# AB.net
KiCad netlist of a schematic drawn in EAGLE
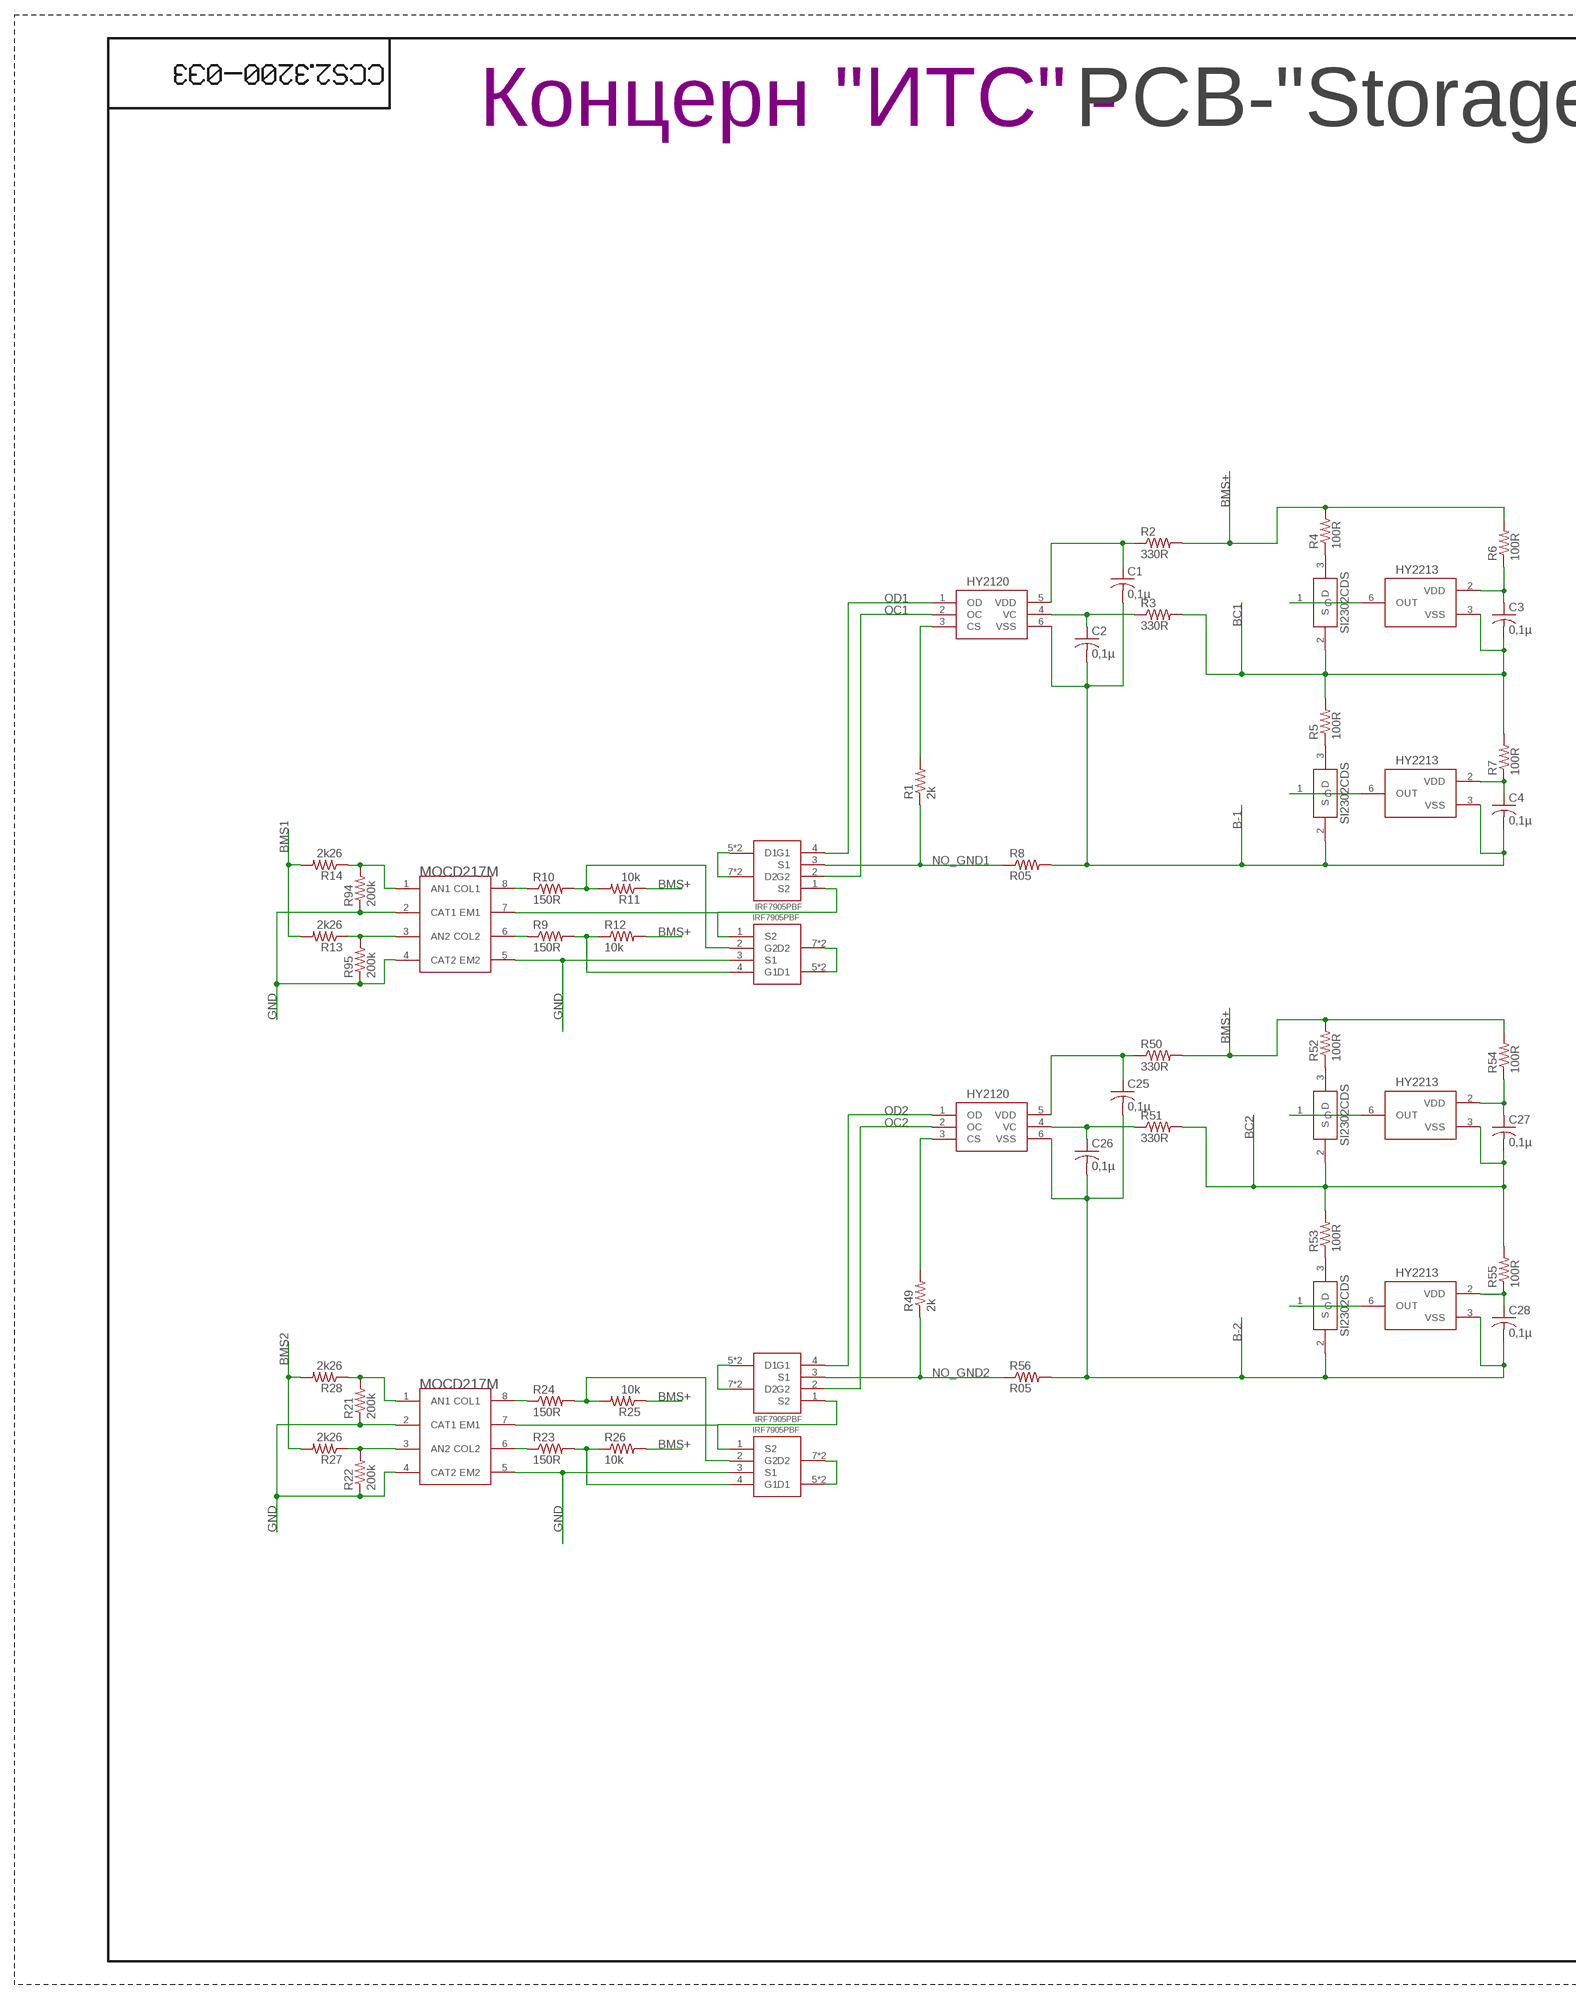
[diagram p0: schematic, sheet 1, part 1 of 2]
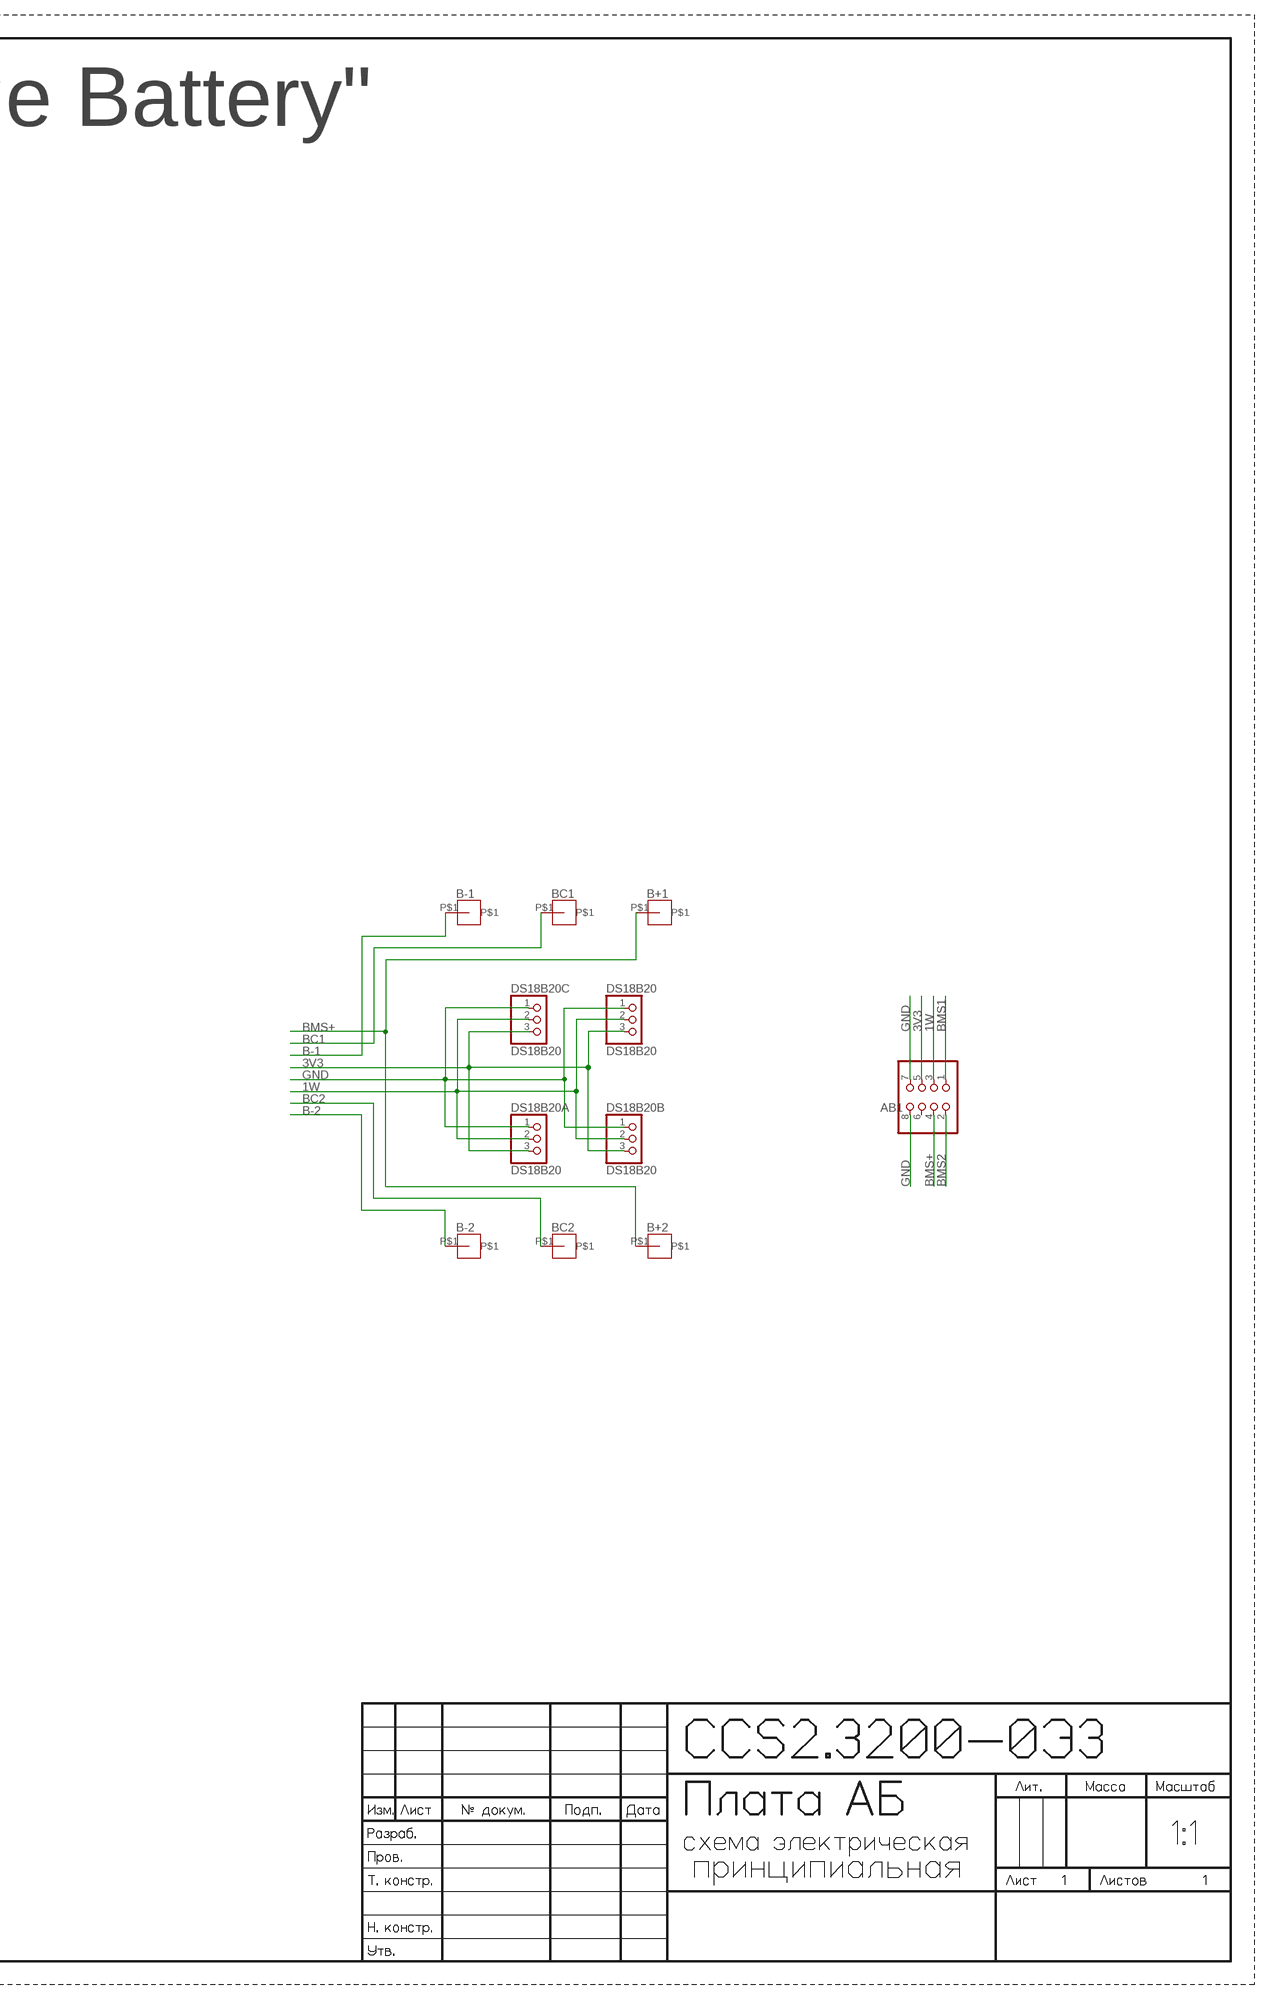
[diagram p1: schematic, sheet 1, part 2 of 2]

(export (version "E")
  (design (tool "Eeschema 10.0.6"))
  (components
    (comp (ref "AB1")
      (value "PINHD-2X4")
      (footprint "eagle-import:2X04")
      (libsource (lib "eagle-import") (part "PINHD-2X4"))
    )
    (comp (ref "B+1")
      (value "BATTERY")
      (footprint "eagle-import:BATTERY")
      (libsource (lib "eagle-import") (part "BATTERY"))
    )
    (comp (ref "B+2")
      (value "BATTERY")
      (footprint "eagle-import:BATTERY")
      (libsource (lib "eagle-import") (part "BATTERY"))
    )
    (comp (ref "B-1")
      (value "BATTERY")
      (footprint "eagle-import:BATTERY")
      (libsource (lib "eagle-import") (part "BATTERY"))
    )
    (comp (ref "B-2")
      (value "BATTERY")
      (footprint "eagle-import:BATTERY")
      (libsource (lib "eagle-import") (part "BATTERY"))
    )
    (comp (ref "BC1")
      (value "BATTERY")
      (footprint "eagle-import:BATTERY")
      (libsource (lib "eagle-import") (part "BATTERY"))
    )
    (comp (ref "BC2")
      (value "BATTERY")
      (footprint "eagle-import:BATTERY")
      (libsource (lib "eagle-import") (part "BATTERY"))
    )
    (comp (ref "C1")
      (value "0,1µ")
      (footprint "eagle-import:C0603")
      (libsource (lib "eagle-import") (part "C-USC0603"))
    )
    (comp (ref "C2")
      (value "0,1µ")
      (footprint "eagle-import:C0603")
      (libsource (lib "eagle-import") (part "C-USC0603"))
    )
    (comp (ref "C3")
      (value "0,1µ")
      (footprint "eagle-import:C0603")
      (libsource (lib "eagle-import") (part "C-USC0603"))
    )
    (comp (ref "C4")
      (value "0,1µ")
      (footprint "eagle-import:C0603")
      (libsource (lib "eagle-import") (part "C-USC0603"))
    )
    (comp (ref "C25")
      (value "0,1µ")
      (footprint "eagle-import:C0603")
      (libsource (lib "eagle-import") (part "C-USC0603"))
    )
    (comp (ref "C26")
      (value "0,1µ")
      (footprint "eagle-import:C0603")
      (libsource (lib "eagle-import") (part "C-USC0603"))
    )
    (comp (ref "C27")
      (value "0,1µ")
      (footprint "eagle-import:C0603")
      (libsource (lib "eagle-import") (part "C-USC0603"))
    )
    (comp (ref "C28")
      (value "0,1µ")
      (footprint "eagle-import:C0603")
      (libsource (lib "eagle-import") (part "C-USC0603"))
    )
    (comp (ref "DS18B20")
      (value "DS18B20")
      (footprint "eagle-import:CONNECT1X3")
      (libsource (lib "eagle-import") (part "CONNECT1X3"))
    )
    (comp (ref "DS18B20A")
      (value "DS18B20")
      (footprint "eagle-import:CONNECT1X3")
      (libsource (lib "eagle-import") (part "CONNECT1X3"))
    )
    (comp (ref "DS18B20B")
      (value "DS18B20")
      (footprint "eagle-import:CONNECT1X3")
      (libsource (lib "eagle-import") (part "CONNECT1X3"))
    )
    (comp (ref "DS18B20C")
      (value "DS18B20")
      (footprint "eagle-import:CONNECT1X3")
      (libsource (lib "eagle-import") (part "CONNECT1X3"))
    )
    (comp (ref "R1")
      (value "2k")
      (footprint "eagle-import:R0603")
      (libsource (lib "eagle-import") (part "resistor_348_R-US_R0603"))
    )
    (comp (ref "R2")
      (value "330R")
      (footprint "eagle-import:R0603")
      (libsource (lib "eagle-import") (part "resistor_348_R-US_R0603"))
    )
    (comp (ref "R3")
      (value "330R")
      (footprint "eagle-import:R0603")
      (libsource (lib "eagle-import") (part "resistor_348_R-US_R0603"))
    )
    (comp (ref "R4")
      (value "100R")
      (footprint "eagle-import:R0603")
      (libsource (lib "eagle-import") (part "resistor_348_R-US_R0603"))
    )
    (comp (ref "R5")
      (value "100R")
      (footprint "eagle-import:R0603")
      (libsource (lib "eagle-import") (part "resistor_348_R-US_R0603"))
    )
    (comp (ref "R6")
      (value "100R")
      (footprint "eagle-import:R0603")
      (libsource (lib "eagle-import") (part "resistor_348_R-US_R0603"))
    )
    (comp (ref "R7")
      (value "100R")
      (footprint "eagle-import:R0603")
      (libsource (lib "eagle-import") (part "resistor_348_R-US_R0603"))
    )
    (comp (ref "R8")
      (value "R05")
      (footprint "eagle-import:R2512")
      (libsource (lib "eagle-import") (part "R-US_R2512"))
    )
    (comp (ref "R9")
      (value "150R")
      (footprint "eagle-import:R0603")
      (libsource (lib "eagle-import") (part "resistor_348_R-US_R0603"))
    )
    (comp (ref "R10")
      (value "150R")
      (footprint "eagle-import:R0603")
      (libsource (lib "eagle-import") (part "resistor_348_R-US_R0603"))
    )
    (comp (ref "R11")
      (value "10k")
      (footprint "eagle-import:R0603")
      (libsource (lib "eagle-import") (part "resistor_348_R-US_R0603"))
    )
    (comp (ref "R12")
      (value "10k")
      (footprint "eagle-import:R0603")
      (libsource (lib "eagle-import") (part "resistor_348_R-US_R0603"))
    )
    (comp (ref "R13")
      (value "2k26")
      (footprint "eagle-import:R0603")
      (libsource (lib "eagle-import") (part "resistor_348_R-US_R0603"))
    )
    (comp (ref "R14")
      (value "2k26")
      (footprint "eagle-import:R0603")
      (libsource (lib "eagle-import") (part "resistor_348_R-US_R0603"))
    )
    (comp (ref "R21")
      (value "200k")
      (footprint "eagle-import:R0603")
      (libsource (lib "eagle-import") (part "resistor_348_R-US_R0603"))
    )
    (comp (ref "R22")
      (value "200k")
      (footprint "eagle-import:R0603")
      (libsource (lib "eagle-import") (part "resistor_348_R-US_R0603"))
    )
    (comp (ref "R23")
      (value "150R")
      (footprint "eagle-import:R0603")
      (libsource (lib "eagle-import") (part "resistor_348_R-US_R0603"))
    )
    (comp (ref "R24")
      (value "150R")
      (footprint "eagle-import:R0603")
      (libsource (lib "eagle-import") (part "resistor_348_R-US_R0603"))
    )
    (comp (ref "R25")
      (value "10k")
      (footprint "eagle-import:R0603")
      (libsource (lib "eagle-import") (part "resistor_348_R-US_R0603"))
    )
    (comp (ref "R26")
      (value "10k")
      (footprint "eagle-import:R0603")
      (libsource (lib "eagle-import") (part "resistor_348_R-US_R0603"))
    )
    (comp (ref "R27")
      (value "2k26")
      (footprint "eagle-import:R0603")
      (libsource (lib "eagle-import") (part "resistor_348_R-US_R0603"))
    )
    (comp (ref "R28")
      (value "2k26")
      (footprint "eagle-import:R0603")
      (libsource (lib "eagle-import") (part "resistor_348_R-US_R0603"))
    )
    (comp (ref "R49")
      (value "2k")
      (footprint "eagle-import:R0603")
      (libsource (lib "eagle-import") (part "resistor_348_R-US_R0603"))
    )
    (comp (ref "R50")
      (value "330R")
      (footprint "eagle-import:R0603")
      (libsource (lib "eagle-import") (part "resistor_348_R-US_R0603"))
    )
    (comp (ref "R51")
      (value "330R")
      (footprint "eagle-import:R0603")
      (libsource (lib "eagle-import") (part "resistor_348_R-US_R0603"))
    )
    (comp (ref "R52")
      (value "100R")
      (footprint "eagle-import:R0603")
      (libsource (lib "eagle-import") (part "resistor_348_R-US_R0603"))
    )
    (comp (ref "R53")
      (value "100R")
      (footprint "eagle-import:R0603")
      (libsource (lib "eagle-import") (part "resistor_348_R-US_R0603"))
    )
    (comp (ref "R54")
      (value "100R")
      (footprint "eagle-import:R0603")
      (libsource (lib "eagle-import") (part "resistor_348_R-US_R0603"))
    )
    (comp (ref "R55")
      (value "100R")
      (footprint "eagle-import:R0603")
      (libsource (lib "eagle-import") (part "resistor_348_R-US_R0603"))
    )
    (comp (ref "R56")
      (value "R05")
      (footprint "eagle-import:R2512")
      (libsource (lib "eagle-import") (part "R-US_R2512"))
    )
    (comp (ref "R94")
      (value "200k")
      (footprint "eagle-import:R0603")
      (libsource (lib "eagle-import") (part "resistor_348_R-US_R0603"))
    )
    (comp (ref "R95")
      (value "200k")
      (footprint "eagle-import:R0603")
      (libsource (lib "eagle-import") (part "resistor_348_R-US_R0603"))
    )
    (comp (ref "U$1")
      (value "PCB-\"Storage Battery\"")
      (footprint "eagle-import:ITS-LOGO")
      (libsource (lib "eagle-import") (part "ITS-LOGOPCB-{dblquote}{dblquote}"))
    )
    (comp (ref "U$2")
      (value "MOCD217M")
      (footprint "eagle-import:SOIC8")
      (libsource (lib "eagle-import") (part "MOCD217M"))
    )
    (comp (ref "U$3")
      (value "HY2120")
      (footprint "eagle-import:SOT23-6")
      (libsource (lib "eagle-import") (part "HY2120"))
    )
    (comp (ref "U$4")
      (value "HY2213\"")
      (footprint "eagle-import:SOT23-6")
      (libsource (lib "eagle-import") (part "HY2213{dblquote}"))
    )
    (comp (ref "U$5")
      (value "HY2213\"")
      (footprint "eagle-import:SOT23-6")
      (libsource (lib "eagle-import") (part "HY2213{dblquote}"))
    )
    (comp (ref "U$6")
      (value "SI2302CDS")
      (footprint "eagle-import:SOT23-3")
      (libsource (lib "eagle-import") (part "SI2302CDS"))
    )
    (comp (ref "U$7")
      (value "SI2302CDS")
      (footprint "eagle-import:SOT23-3")
      (libsource (lib "eagle-import") (part "SI2302CDS"))
    )
    (comp (ref "U$8")
      (value "IRF7905PBF")
      (footprint "eagle-import:SO8")
      (libsource (lib "eagle-import") (part "IRF7905PBF"))
    )
    (comp (ref "U$9")
      (value "IRF7905PBF")
      (footprint "eagle-import:SO8")
      (libsource (lib "eagle-import") (part "IRF7905PBF"))
    )
    (comp (ref "U$11")
      (value "MOCD217M")
      (footprint "eagle-import:SOIC8")
      (libsource (lib "eagle-import") (part "MOCD217M"))
    )
    (comp (ref "U$12")
      (value "IRF7905PBF")
      (footprint "eagle-import:SO8")
      (libsource (lib "eagle-import") (part "IRF7905PBF"))
    )
    (comp (ref "U$13")
      (value "IRF7905PBF")
      (footprint "eagle-import:SO8")
      (libsource (lib "eagle-import") (part "IRF7905PBF"))
    )
    (comp (ref "U$45")
      (value "HY2120")
      (footprint "eagle-import:SOT23-6")
      (libsource (lib "eagle-import") (part "HY2120"))
    )
    (comp (ref "U$46")
      (value "HY2213\"")
      (footprint "eagle-import:SOT23-6")
      (libsource (lib "eagle-import") (part "HY2213{dblquote}"))
    )
    (comp (ref "U$47")
      (value "HY2213\"")
      (footprint "eagle-import:SOT23-6")
      (libsource (lib "eagle-import") (part "HY2213{dblquote}"))
    )
    (comp (ref "U$48")
      (value "SI2302CDS")
      (footprint "eagle-import:SOT23-3")
      (libsource (lib "eagle-import") (part "SI2302CDS"))
    )
    (comp (ref "U$49")
      (value "SI2302CDS")
      (footprint "eagle-import:SOT23-3")
      (libsource (lib "eagle-import") (part "SI2302CDS"))
    )
  )
  (nets
    (net (code "1") (name "/1W") (class "Default")
      (node (ref "AB1") (pin "3") (pinfunction "3_3") (pintype "passive"))
      (node (ref "DS18B20") (pin "2") (pinfunction "2_2") (pintype "passive"))
      (node (ref "DS18B20A") (pin "2") (pinfunction "2_2") (pintype "passive"))
      (node (ref "DS18B20B") (pin "2") (pinfunction "2_2") (pintype "passive"))
      (node (ref "DS18B20C") (pin "2") (pinfunction "2_2") (pintype "passive"))
    )
    (net (code "2") (name "/3V3") (class "Default")
      (node (ref "AB1") (pin "5") (pinfunction "5_5") (pintype "passive"))
      (node (ref "DS18B20") (pin "3") (pinfunction "3_3") (pintype "passive"))
      (node (ref "DS18B20A") (pin "3") (pinfunction "3_3") (pintype "passive"))
      (node (ref "DS18B20B") (pin "3") (pinfunction "3_3") (pintype "passive"))
      (node (ref "DS18B20C") (pin "3") (pinfunction "3_3") (pintype "passive"))
    )
    (net (code "3") (name "/B-1") (class "Default")
      (node (ref "B-1") (pin "P$1") (pinfunction "P$1_P$1") (pintype "bidirectional"))
      (node (ref "C1") (pin "2") (pinfunction "2_2") (pintype "passive"))
      (node (ref "C2") (pin "2") (pinfunction "2_2") (pintype "passive"))
      (node (ref "C4") (pin "2") (pinfunction "2_2") (pintype "passive"))
      (node (ref "R8") (pin "2") (pinfunction "2_2") (pintype "passive"))
      (node (ref "U$3") (pin "6") (pinfunction "VSS_6") (pintype "bidirectional"))
      (node (ref "U$5") (pin "3") (pinfunction "VSS_3") (pintype "bidirectional"))
      (node (ref "U$7") (pin "2") (pinfunction "S_2") (pintype "bidirectional"))
    )
    (net (code "4") (name "/B-2") (class "Default")
      (node (ref "B-2") (pin "P$1") (pinfunction "P$1_P$1") (pintype "bidirectional"))
      (node (ref "C25") (pin "2") (pinfunction "2_2") (pintype "passive"))
      (node (ref "C26") (pin "2") (pinfunction "2_2") (pintype "passive"))
      (node (ref "C28") (pin "2") (pinfunction "2_2") (pintype "passive"))
      (node (ref "R56") (pin "2") (pinfunction "2_2") (pintype "passive"))
      (node (ref "U$45") (pin "6") (pinfunction "VSS_6") (pintype "bidirectional"))
      (node (ref "U$47") (pin "3") (pinfunction "VSS_3") (pintype "bidirectional"))
      (node (ref "U$49") (pin "2") (pinfunction "S_2") (pintype "bidirectional"))
    )
    (net (code "5") (name "/BC1") (class "Default")
      (node (ref "BC1") (pin "P$1") (pinfunction "P$1_P$1") (pintype "bidirectional"))
      (node (ref "C3") (pin "2") (pinfunction "2_2") (pintype "passive"))
      (node (ref "R3") (pin "2") (pinfunction "2_2") (pintype "passive"))
      (node (ref "R5") (pin "2") (pinfunction "2_2") (pintype "passive"))
      (node (ref "R7") (pin "2") (pinfunction "2_2") (pintype "passive"))
      (node (ref "U$4") (pin "3") (pinfunction "VSS_3") (pintype "bidirectional"))
      (node (ref "U$6") (pin "2") (pinfunction "S_2") (pintype "bidirectional"))
    )
    (net (code "6") (name "/BC2") (class "Default")
      (node (ref "BC2") (pin "P$1") (pinfunction "P$1_P$1") (pintype "bidirectional"))
      (node (ref "C27") (pin "2") (pinfunction "2_2") (pintype "passive"))
      (node (ref "R51") (pin "2") (pinfunction "2_2") (pintype "passive"))
      (node (ref "R53") (pin "2") (pinfunction "2_2") (pintype "passive"))
      (node (ref "R55") (pin "2") (pinfunction "2_2") (pintype "passive"))
      (node (ref "U$46") (pin "3") (pinfunction "VSS_3") (pintype "bidirectional"))
      (node (ref "U$48") (pin "2") (pinfunction "S_2") (pintype "bidirectional"))
    )
    (net (code "7") (name "/BMS+") (class "Default")
      (node (ref "AB1") (pin "4") (pinfunction "4_4") (pintype "passive"))
      (node (ref "B+1") (pin "P$1") (pinfunction "P$1_P$1") (pintype "bidirectional"))
      (node (ref "B+2") (pin "P$1") (pinfunction "P$1_P$1") (pintype "bidirectional"))
      (node (ref "R11") (pin "1") (pinfunction "1_1") (pintype "passive"))
      (node (ref "R12") (pin "2") (pinfunction "2_2") (pintype "passive"))
      (node (ref "R2") (pin "2") (pinfunction "2_2") (pintype "passive"))
      (node (ref "R25") (pin "1") (pinfunction "1_1") (pintype "passive"))
      (node (ref "R26") (pin "2") (pinfunction "2_2") (pintype "passive"))
      (node (ref "R4") (pin "2") (pinfunction "2_2") (pintype "passive"))
      (node (ref "R50") (pin "2") (pinfunction "2_2") (pintype "passive"))
      (node (ref "R52") (pin "2") (pinfunction "2_2") (pintype "passive"))
      (node (ref "R54") (pin "2") (pinfunction "2_2") (pintype "passive"))
      (node (ref "R6") (pin "2") (pinfunction "2_2") (pintype "passive"))
    )
    (net (code "8") (name "/BMS1") (class "Default")
      (node (ref "AB1") (pin "1") (pinfunction "1_1") (pintype "passive"))
      (node (ref "R13") (pin "2") (pinfunction "2_2") (pintype "passive"))
      (node (ref "R14") (pin "2") (pinfunction "2_2") (pintype "passive"))
    )
    (net (code "9") (name "/BMS2") (class "Default")
      (node (ref "AB1") (pin "2") (pinfunction "2_2") (pintype "passive"))
      (node (ref "R27") (pin "2") (pinfunction "2_2") (pintype "passive"))
      (node (ref "R28") (pin "2") (pinfunction "2_2") (pintype "passive"))
    )
    (net (code "10") (name "/GND") (class "Default")
      (node (ref "AB1") (pin "7") (pinfunction "7_7") (pintype "passive"))
      (node (ref "AB1") (pin "8") (pinfunction "8_8") (pintype "passive"))
      (node (ref "DS18B20") (pin "1") (pinfunction "1_1") (pintype "passive"))
      (node (ref "DS18B20A") (pin "1") (pinfunction "1_1") (pintype "passive"))
      (node (ref "DS18B20B") (pin "1") (pinfunction "1_1") (pintype "passive"))
      (node (ref "DS18B20C") (pin "1") (pinfunction "1_1") (pintype "passive"))
      (node (ref "R21") (pin "1") (pinfunction "1_1") (pintype "passive"))
      (node (ref "R22") (pin "1") (pinfunction "1_1") (pintype "passive"))
      (node (ref "R94") (pin "1") (pinfunction "1_1") (pintype "passive"))
      (node (ref "R95") (pin "1") (pinfunction "1_1") (pintype "passive"))
      (node (ref "U$11") (pin "2") (pinfunction "CAT1_2") (pintype "bidirectional"))
      (node (ref "U$11") (pin "4") (pinfunction "CAT2_4") (pintype "bidirectional"))
      (node (ref "U$11") (pin "5") (pinfunction "EM2_5") (pintype "bidirectional"))
      (node (ref "U$12") (pin "3") (pinfunction "S1_3") (pintype "bidirectional"))
      (node (ref "U$2") (pin "2") (pinfunction "CAT1_2") (pintype "bidirectional"))
      (node (ref "U$2") (pin "4") (pinfunction "CAT2_4") (pintype "bidirectional"))
      (node (ref "U$2") (pin "5") (pinfunction "EM2_5") (pintype "bidirectional"))
      (node (ref "U$8") (pin "3") (pinfunction "S1_3") (pintype "bidirectional"))
    )
    (net (code "11") (name "/NO_GND1") (class "Default")
      (node (ref "R1") (pin "1") (pinfunction "1_1") (pintype "passive"))
      (node (ref "R8") (pin "1") (pinfunction "1_1") (pintype "passive"))
      (node (ref "U$9") (pin "3") (pinfunction "S1_3") (pintype "bidirectional"))
    )
    (net (code "12") (name "/NO_GND2") (class "Default")
      (node (ref "R49") (pin "1") (pinfunction "1_1") (pintype "passive"))
      (node (ref "R56") (pin "1") (pinfunction "1_1") (pintype "passive"))
      (node (ref "U$13") (pin "3") (pinfunction "S1_3") (pintype "bidirectional"))
    )
    (net (code "13") (name "/OC1") (class "Default")
      (node (ref "U$3") (pin "2") (pinfunction "OC_2") (pintype "bidirectional"))
      (node (ref "U$9") (pin "2") (pinfunction "G2_2") (pintype "bidirectional"))
    )
    (net (code "14") (name "/OC2") (class "Default")
      (node (ref "U$13") (pin "2") (pinfunction "G2_2") (pintype "bidirectional"))
      (node (ref "U$45") (pin "2") (pinfunction "OC_2") (pintype "bidirectional"))
    )
    (net (code "15") (name "/OD1") (class "Default")
      (node (ref "U$3") (pin "1") (pinfunction "OD_1") (pintype "bidirectional"))
      (node (ref "U$9") (pin "4") (pinfunction "G1_4") (pintype "bidirectional"))
    )
    (net (code "16") (name "/OD2") (class "Default")
      (node (ref "U$13") (pin "4") (pinfunction "G1_4") (pintype "bidirectional"))
      (node (ref "U$45") (pin "1") (pinfunction "OD_1") (pintype "bidirectional"))
    )
    (net (code "17") (name "Net-(U$2-AN1)") (class "Default")
      (node (ref "R14") (pin "1") (pinfunction "1_1") (pintype "passive"))
      (node (ref "R94") (pin "2") (pinfunction "2_2") (pintype "passive"))
      (node (ref "U$2") (pin "1") (pinfunction "AN1_1") (pintype "bidirectional"))
    )
    (net (code "18") (name "Net-(U$2-AN2)") (class "Default")
      (node (ref "R13") (pin "1") (pinfunction "1_1") (pintype "passive"))
      (node (ref "R95") (pin "2") (pinfunction "2_2") (pintype "passive"))
      (node (ref "U$2") (pin "3") (pinfunction "AN2_3") (pintype "bidirectional"))
    )
    (net (code "19") (name "Net-(U$2-COL1)") (class "Default")
      (node (ref "R10") (pin "1") (pinfunction "1_1") (pintype "passive"))
      (node (ref "U$2") (pin "8") (pinfunction "COL1_8") (pintype "bidirectional"))
    )
    (net (code "20") (name "Net-(U$2-COL2)") (class "Default")
      (node (ref "R9") (pin "1") (pinfunction "1_1") (pintype "passive"))
      (node (ref "U$2") (pin "6") (pinfunction "COL2_6") (pintype "bidirectional"))
    )
    (net (code "21") (name "Net-(U$2-EM1)") (class "Default")
      (node (ref "U$2") (pin "7") (pinfunction "EM1_7") (pintype "bidirectional"))
      (node (ref "U$8") (pin "1") (pinfunction "S2_1") (pintype "bidirectional"))
      (node (ref "U$9") (pin "1") (pinfunction "S2_1") (pintype "bidirectional"))
    )
    (net (code "22") (name "Net-(U$3-CS)") (class "Default")
      (node (ref "R1") (pin "2") (pinfunction "2_2") (pintype "passive"))
      (node (ref "U$3") (pin "3") (pinfunction "CS_3") (pintype "bidirectional"))
    )
    (net (code "23") (name "Net-(U$3-VC)") (class "Default")
      (node (ref "C2") (pin "1") (pinfunction "1_1") (pintype "passive"))
      (node (ref "R3") (pin "1") (pinfunction "1_1") (pintype "passive"))
      (node (ref "U$3") (pin "4") (pinfunction "VC_4") (pintype "bidirectional"))
    )
    (net (code "24") (name "Net-(U$3-VDD)") (class "Default")
      (node (ref "C1") (pin "1") (pinfunction "1_1") (pintype "passive"))
      (node (ref "R2") (pin "1") (pinfunction "1_1") (pintype "passive"))
      (node (ref "U$3") (pin "5") (pinfunction "VDD_5") (pintype "bidirectional"))
    )
    (net (code "25") (name "Net-(U$4-OUT)") (class "Default")
      (node (ref "U$4") (pin "6") (pinfunction "OUT_6") (pintype "bidirectional"))
      (node (ref "U$6") (pin "1") (pinfunction "G_1") (pintype "bidirectional"))
    )
    (net (code "26") (name "Net-(U$4-VDD)") (class "Default")
      (node (ref "C3") (pin "1") (pinfunction "1_1") (pintype "passive"))
      (node (ref "R6") (pin "1") (pinfunction "1_1") (pintype "passive"))
      (node (ref "U$4") (pin "2") (pinfunction "VDD_2") (pintype "bidirectional"))
    )
    (net (code "27") (name "Net-(U$5-OUT)") (class "Default")
      (node (ref "U$5") (pin "6") (pinfunction "OUT_6") (pintype "bidirectional"))
      (node (ref "U$7") (pin "1") (pinfunction "G_1") (pintype "bidirectional"))
    )
    (net (code "28") (name "Net-(U$5-VDD)") (class "Default")
      (node (ref "C4") (pin "1") (pinfunction "1_1") (pintype "passive"))
      (node (ref "R7") (pin "1") (pinfunction "1_1") (pintype "passive"))
      (node (ref "U$5") (pin "2") (pinfunction "VDD_2") (pintype "bidirectional"))
    )
    (net (code "29") (name "Net-(U$6-D)") (class "Default")
      (node (ref "R4") (pin "1") (pinfunction "1_1") (pintype "passive"))
      (node (ref "U$6") (pin "3") (pinfunction "D_3") (pintype "bidirectional"))
    )
    (net (code "30") (name "Net-(U$7-D)") (class "Default")
      (node (ref "R5") (pin "1") (pinfunction "1_1") (pintype "passive"))
      (node (ref "U$7") (pin "3") (pinfunction "D_3") (pintype "bidirectional"))
    )
    (net (code "31") (name "Net-(U$8-D1-Pad5)") (class "Default")
      (node (ref "U$8") (pin "5") (pinfunction "D1_5") (pintype "bidirectional"))
      (node (ref "U$8") (pin "6") (pinfunction "D1_6") (pintype "bidirectional"))
      (node (ref "U$8") (pin "7") (pinfunction "D2_7") (pintype "bidirectional"))
      (node (ref "U$8") (pin "8") (pinfunction "D2_8") (pintype "bidirectional"))
    )
    (net (code "32") (name "Net-(U$8-G1)") (class "Default")
      (node (ref "R12") (pin "1") (pinfunction "1_1") (pintype "passive"))
      (node (ref "R9") (pin "2") (pinfunction "2_2") (pintype "passive"))
      (node (ref "U$8") (pin "4") (pinfunction "G1_4") (pintype "bidirectional"))
    )
    (net (code "33") (name "Net-(U$8-G2)") (class "Default")
      (node (ref "R10") (pin "2") (pinfunction "2_2") (pintype "passive"))
      (node (ref "R11") (pin "2") (pinfunction "2_2") (pintype "passive"))
      (node (ref "U$8") (pin "2") (pinfunction "G2_2") (pintype "bidirectional"))
    )
    (net (code "34") (name "Net-(U$9-D1-Pad5)") (class "Default")
      (node (ref "U$9") (pin "5") (pinfunction "D1_5") (pintype "bidirectional"))
      (node (ref "U$9") (pin "6") (pinfunction "D1_6") (pintype "bidirectional"))
      (node (ref "U$9") (pin "7") (pinfunction "D2_7") (pintype "bidirectional"))
      (node (ref "U$9") (pin "8") (pinfunction "D2_8") (pintype "bidirectional"))
    )
    (net (code "35") (name "Net-(U$11-AN1)") (class "Default")
      (node (ref "R21") (pin "2") (pinfunction "2_2") (pintype "passive"))
      (node (ref "R28") (pin "1") (pinfunction "1_1") (pintype "passive"))
      (node (ref "U$11") (pin "1") (pinfunction "AN1_1") (pintype "bidirectional"))
    )
    (net (code "36") (name "Net-(U$11-AN2)") (class "Default")
      (node (ref "R22") (pin "2") (pinfunction "2_2") (pintype "passive"))
      (node (ref "R27") (pin "1") (pinfunction "1_1") (pintype "passive"))
      (node (ref "U$11") (pin "3") (pinfunction "AN2_3") (pintype "bidirectional"))
    )
    (net (code "37") (name "Net-(U$11-COL1)") (class "Default")
      (node (ref "R24") (pin "1") (pinfunction "1_1") (pintype "passive"))
      (node (ref "U$11") (pin "8") (pinfunction "COL1_8") (pintype "bidirectional"))
    )
    (net (code "38") (name "Net-(U$11-COL2)") (class "Default")
      (node (ref "R23") (pin "1") (pinfunction "1_1") (pintype "passive"))
      (node (ref "U$11") (pin "6") (pinfunction "COL2_6") (pintype "bidirectional"))
    )
    (net (code "39") (name "Net-(U$11-EM1)") (class "Default")
      (node (ref "U$11") (pin "7") (pinfunction "EM1_7") (pintype "bidirectional"))
      (node (ref "U$12") (pin "1") (pinfunction "S2_1") (pintype "bidirectional"))
      (node (ref "U$13") (pin "1") (pinfunction "S2_1") (pintype "bidirectional"))
    )
    (net (code "40") (name "Net-(U$12-D1-Pad5)") (class "Default")
      (node (ref "U$12") (pin "5") (pinfunction "D1_5") (pintype "bidirectional"))
      (node (ref "U$12") (pin "6") (pinfunction "D1_6") (pintype "bidirectional"))
      (node (ref "U$12") (pin "7") (pinfunction "D2_7") (pintype "bidirectional"))
      (node (ref "U$12") (pin "8") (pinfunction "D2_8") (pintype "bidirectional"))
    )
    (net (code "41") (name "Net-(U$12-G1)") (class "Default")
      (node (ref "R23") (pin "2") (pinfunction "2_2") (pintype "passive"))
      (node (ref "R26") (pin "1") (pinfunction "1_1") (pintype "passive"))
      (node (ref "U$12") (pin "4") (pinfunction "G1_4") (pintype "bidirectional"))
    )
    (net (code "42") (name "Net-(U$12-G2)") (class "Default")
      (node (ref "R24") (pin "2") (pinfunction "2_2") (pintype "passive"))
      (node (ref "R25") (pin "2") (pinfunction "2_2") (pintype "passive"))
      (node (ref "U$12") (pin "2") (pinfunction "G2_2") (pintype "bidirectional"))
    )
    (net (code "43") (name "Net-(U$13-D1-Pad5)") (class "Default")
      (node (ref "U$13") (pin "5") (pinfunction "D1_5") (pintype "bidirectional"))
      (node (ref "U$13") (pin "6") (pinfunction "D1_6") (pintype "bidirectional"))
      (node (ref "U$13") (pin "7") (pinfunction "D2_7") (pintype "bidirectional"))
      (node (ref "U$13") (pin "8") (pinfunction "D2_8") (pintype "bidirectional"))
    )
    (net (code "44") (name "Net-(U$45-CS)") (class "Default")
      (node (ref "R49") (pin "2") (pinfunction "2_2") (pintype "passive"))
      (node (ref "U$45") (pin "3") (pinfunction "CS_3") (pintype "bidirectional"))
    )
    (net (code "45") (name "Net-(U$45-VC)") (class "Default")
      (node (ref "C26") (pin "1") (pinfunction "1_1") (pintype "passive"))
      (node (ref "R51") (pin "1") (pinfunction "1_1") (pintype "passive"))
      (node (ref "U$45") (pin "4") (pinfunction "VC_4") (pintype "bidirectional"))
    )
    (net (code "46") (name "Net-(U$45-VDD)") (class "Default")
      (node (ref "C25") (pin "1") (pinfunction "1_1") (pintype "passive"))
      (node (ref "R50") (pin "1") (pinfunction "1_1") (pintype "passive"))
      (node (ref "U$45") (pin "5") (pinfunction "VDD_5") (pintype "bidirectional"))
    )
    (net (code "47") (name "Net-(U$46-OUT)") (class "Default")
      (node (ref "U$46") (pin "6") (pinfunction "OUT_6") (pintype "bidirectional"))
      (node (ref "U$48") (pin "1") (pinfunction "G_1") (pintype "bidirectional"))
    )
    (net (code "48") (name "Net-(U$46-VDD)") (class "Default")
      (node (ref "C27") (pin "1") (pinfunction "1_1") (pintype "passive"))
      (node (ref "R54") (pin "1") (pinfunction "1_1") (pintype "passive"))
      (node (ref "U$46") (pin "2") (pinfunction "VDD_2") (pintype "bidirectional"))
    )
    (net (code "49") (name "Net-(U$47-OUT)") (class "Default")
      (node (ref "U$47") (pin "6") (pinfunction "OUT_6") (pintype "bidirectional"))
      (node (ref "U$49") (pin "1") (pinfunction "G_1") (pintype "bidirectional"))
    )
    (net (code "50") (name "Net-(U$47-VDD)") (class "Default")
      (node (ref "C28") (pin "1") (pinfunction "1_1") (pintype "passive"))
      (node (ref "R55") (pin "1") (pinfunction "1_1") (pintype "passive"))
      (node (ref "U$47") (pin "2") (pinfunction "VDD_2") (pintype "bidirectional"))
    )
    (net (code "51") (name "Net-(U$48-D)") (class "Default")
      (node (ref "R52") (pin "1") (pinfunction "1_1") (pintype "passive"))
      (node (ref "U$48") (pin "3") (pinfunction "D_3") (pintype "bidirectional"))
    )
    (net (code "52") (name "Net-(U$49-D)") (class "Default")
      (node (ref "R53") (pin "1") (pinfunction "1_1") (pintype "passive"))
      (node (ref "U$49") (pin "3") (pinfunction "D_3") (pintype "bidirectional"))
    )
    (net (code "53") (name "unconnected-(AB1-Pad6)") (class "Default")
      (node (ref "AB1") (pin "6") (pinfunction "6_6") (pintype "passive"))
    )
  )
)
